# LPC1768_3.net
KiCad netlist of a schematic drawn in Altium Designer
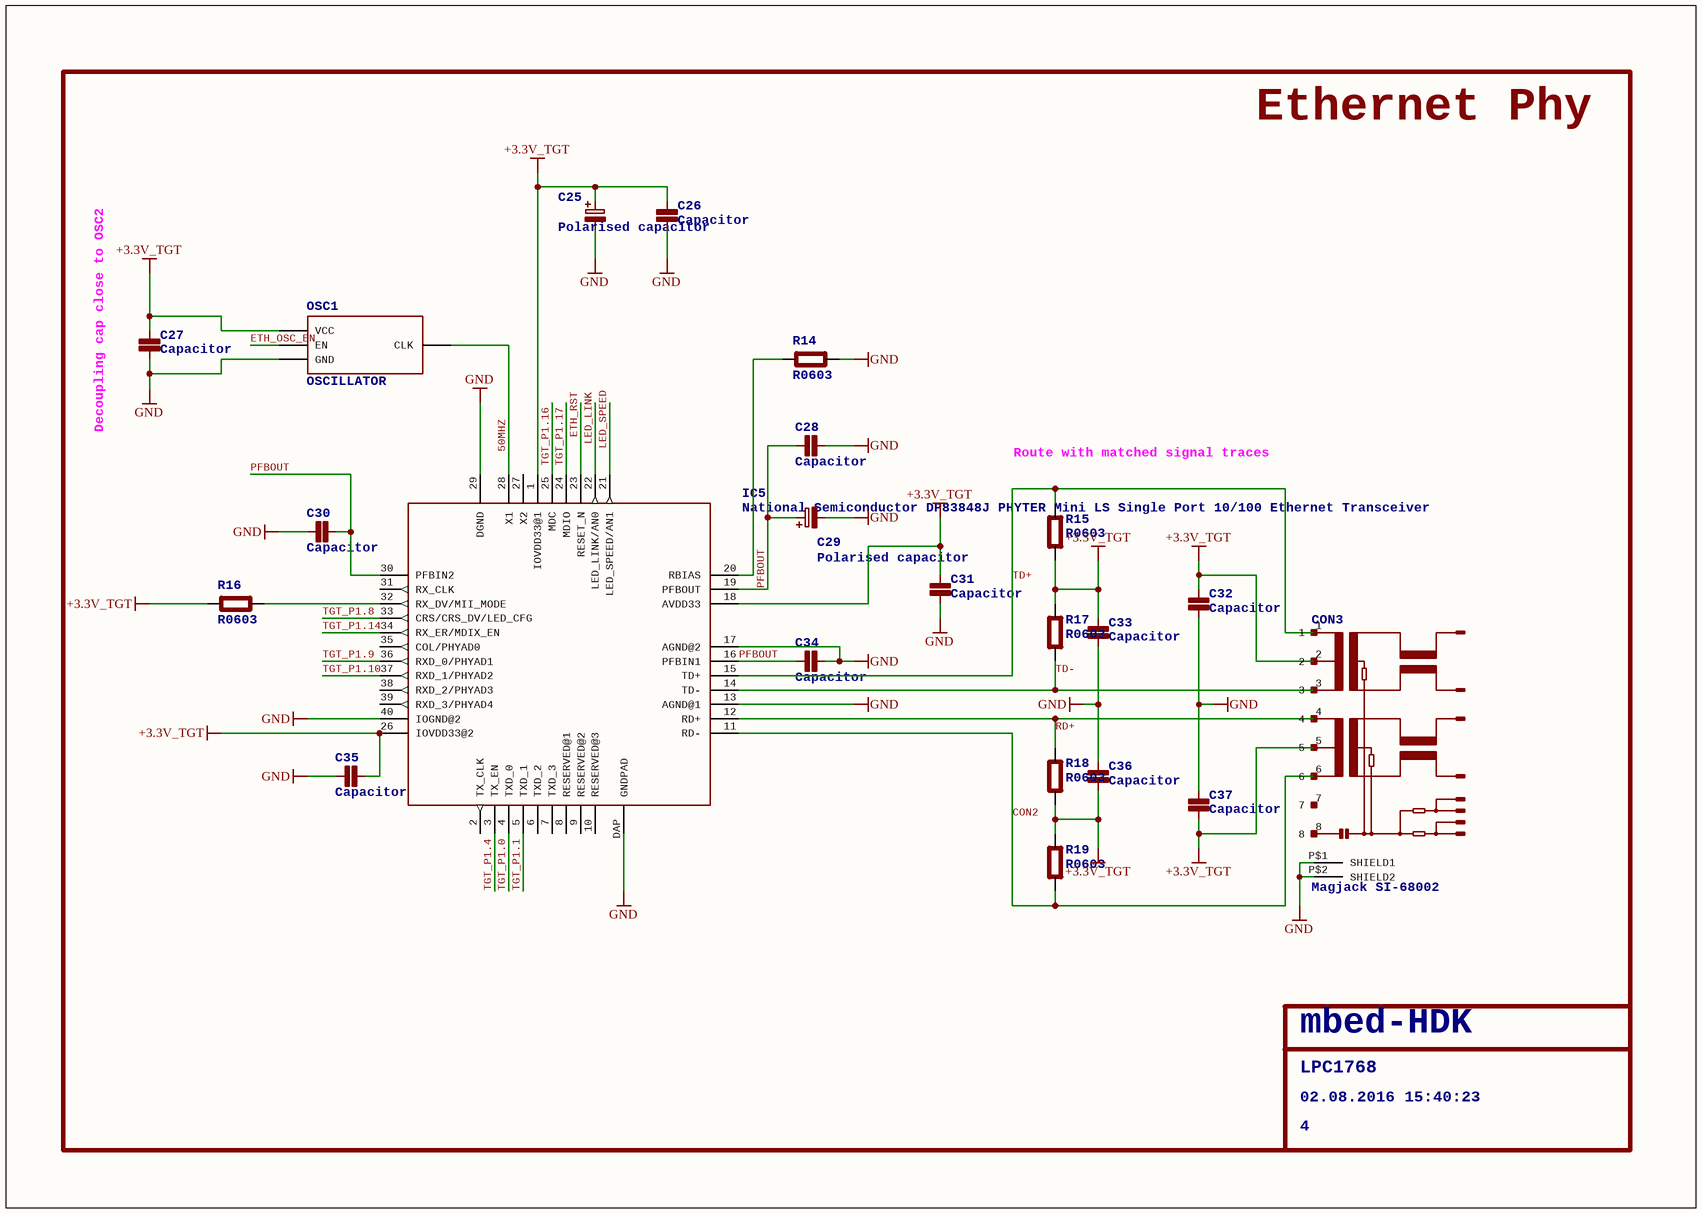
[diagram p0: LPC1768_3.SchDoc]

(export (version "E")
  (design (tool "Eeschema 10.0.6"))
  (components
    (comp (ref "C25")
      (value "Polarised capacitor")
      (footprint "CASE-B")
      (libsource (lib "mbed-HDK") (part "C-POLB"))
    )
    (comp (ref "C26") (value "Capacitor") (footprint "0603") (libsource (lib "mbed-HDK") (part "C0603")))
    (comp (ref "C27") (value "Capacitor") (footprint "0603") (libsource (lib "mbed-HDK") (part "C0603")))
    (comp (ref "C28") (value "Capacitor") (footprint "0603") (libsource (lib "") (part "C0603_2")))
    (comp (ref "C29")
      (value "Polarised capacitor")
      (footprint "CASE-B")
      (libsource (lib "") (part "C-POLB_1"))
    )
    (comp (ref "C30") (value "Capacitor") (footprint "0603") (libsource (lib "") (part "C0603_1")))
    (comp (ref "C31") (value "Capacitor") (footprint "0603") (libsource (lib "mbed-HDK") (part "C0603")))
    (comp (ref "C32") (value "Capacitor") (footprint "0603") (libsource (lib "mbed-HDK") (part "C0603")))
    (comp (ref "C33") (value "Capacitor") (footprint "0603") (libsource (lib "mbed-HDK") (part "C0603")))
    (comp (ref "C34") (value "Capacitor") (footprint "0603") (libsource (lib "") (part "C0603_1")))
    (comp (ref "C35") (value "Capacitor") (footprint "0603") (libsource (lib "") (part "C0603_2")))
    (comp (ref "C36") (value "Capacitor") (footprint "0603") (libsource (lib "mbed-HDK") (part "C0603")))
    (comp (ref "C37") (value "Capacitor") (footprint "0603") (libsource (lib "mbed-HDK") (part "C0603")))
    (comp (ref "CON3")
      (value "Magjack SI-68002")
      (footprint "RJ45")
      (libsource (lib "mbed-HDK") (part "RJ45"))
    )
    (comp (ref "IC5")
      (value "National Semiconductor DP83848J PHYTER Mini LS Single Port 10/100 Ethernet Transceiver")
      (footprint "LLP-40")
      (libsource (lib "mbed-HDK") (part "DP83848J"))
    )
    (comp (ref "OSC1")
      (value "OSCILLATOR")
      (footprint "3.2X.2.5")
      (libsource (lib "mbed-HDK") (part "OSCILLATOR"))
    )
    (comp (ref "R14") (value "R0603") (footprint "0603") (libsource (lib "mbed-HDK") (part "R0603")))
    (comp (ref "R15") (value "R0603") (footprint "0603") (libsource (lib "mbed-HDK") (part "R0603")))
    (comp (ref "R16") (value "R0603") (footprint "0603") (libsource (lib "mbed-HDK") (part "R0603")))
    (comp (ref "R17") (value "R0603") (footprint "0603") (libsource (lib "mbed-HDK") (part "R0603")))
    (comp (ref "R18") (value "R0603") (footprint "0603") (libsource (lib "mbed-HDK") (part "R0603")))
    (comp (ref "R19") (value "R0603") (footprint "0603") (libsource (lib "mbed-HDK") (part "R0603")))
  )
  (nets
    (net (code "1") (name "+3.3V_TGT") (class "Default")
      (node (ref "C25") (pin "1") (pinfunction "1_1") (pintype "passive"))
      (node (ref "C26") (pin "1") (pinfunction "P$1_1") (pintype "passive"))
      (node (ref "C27") (pin "1") (pinfunction "P$1_1") (pintype "passive"))
      (node (ref "C31") (pin "1") (pinfunction "P$1_1") (pintype "passive"))
      (node (ref "C32") (pin "1") (pinfunction "P$1_1") (pintype "passive"))
      (node (ref "C33") (pin "1") (pinfunction "P$1_1") (pintype "passive"))
      (node (ref "C35") (pin "1") (pinfunction "P$1_1") (pintype "passive"))
      (node (ref "C36") (pin "2") (pinfunction "P$2_2") (pintype "passive"))
      (node (ref "C37") (pin "2") (pinfunction "P$2_2") (pintype "passive"))
      (node (ref "CON3") (pin "2") (pinfunction "2_2") (pintype "passive"))
      (node (ref "CON3") (pin "5") (pinfunction "5_5") (pintype "passive"))
      (node (ref "IC5") (pin "1") (pinfunction "IOVDD33@1_1") (pintype "power_in"))
      (node (ref "IC5") (pin "18") (pinfunction "AVDD33_18") (pintype "power_in"))
      (node (ref "IC5") (pin "26") (pinfunction "IOVDD33@2_26") (pintype "power_in"))
      (node (ref "OSC1") (pin "P$4") (pinfunction "VCC_P$4") (pintype "passive"))
      (node (ref "R15") (pin "1") (pinfunction "P$1_1") (pintype "passive"))
      (node (ref "R16") (pin "1") (pinfunction "P$1_1") (pintype "passive"))
      (node (ref "R17") (pin "2") (pinfunction "P$2_2") (pintype "passive"))
      (node (ref "R18") (pin "1") (pinfunction "P$1_1") (pintype "passive"))
      (node (ref "R19") (pin "2") (pinfunction "P$2_2") (pintype "passive"))
    )
    (net (code "2") (name "/50MHZ") (class "Default")
      (node (ref "IC5") (pin "28") (pinfunction "X1_28") (pintype "passive"))
      (node (ref "OSC1") (pin "P$3") (pinfunction "CLK_P$3") (pintype "passive"))
    )
    (net (code "3") (name "/CON2") (class "Default")
      (node (ref "CON3") (pin "6") (pinfunction "6_6") (pintype "passive"))
      (node (ref "IC5") (pin "11") (pinfunction "RD-_11") (pintype "passive"))
      (node (ref "R19") (pin "1") (pinfunction "P$1_1") (pintype "passive"))
    )
    (net (code "4") (name "/ETH_OSC_EN") (class "Default")
      (node (ref "OSC1") (pin "P$1") (pinfunction "EN_P$1") (pintype "passive"))
    )
    (net (code "5") (name "/ETH_RST") (class "Default")
      (node (ref "IC5") (pin "23") (pinfunction "RESET_N_23") (pintype "passive"))
    )
    (net (code "6") (name "/LED_LINK") (class "Default")
      (node (ref "IC5") (pin "22") (pinfunction "LED_LINK/AN0_22") (pintype "output"))
    )
    (net (code "7") (name "/LED_SPEED") (class "Default")
      (node (ref "IC5") (pin "21") (pinfunction "LED_SPEED/AN1_21") (pintype "output"))
    )
    (net (code "8") (name "/PFBOUT") (class "Default")
      (node (ref "C28") (pin "2") (pinfunction "P$2_2") (pintype "passive"))
      (node (ref "C29") (pin "1") (pinfunction "1_1") (pintype "passive"))
      (node (ref "C30") (pin "2") (pinfunction "P$2_2") (pintype "passive"))
      (node (ref "C34") (pin "1") (pinfunction "P$1_1") (pintype "passive"))
      (node (ref "IC5") (pin "16") (pinfunction "PFBIN1_16") (pintype "passive"))
      (node (ref "IC5") (pin "19") (pinfunction "PFBOUT_19") (pintype "passive"))
      (node (ref "IC5") (pin "30") (pinfunction "PFBIN2_30") (pintype "passive"))
    )
    (net (code "9") (name "/RD+") (class "Default")
      (node (ref "CON3") (pin "4") (pinfunction "4_4") (pintype "passive"))
      (node (ref "IC5") (pin "12") (pinfunction "RD+_12") (pintype "passive"))
      (node (ref "R18") (pin "2") (pinfunction "P$2_2") (pintype "passive"))
    )
    (net (code "10") (name "/TD+") (class "Default")
      (node (ref "CON3") (pin "1") (pinfunction "1_1") (pintype "passive"))
      (node (ref "IC5") (pin "15") (pinfunction "TD+_15") (pintype "passive"))
      (node (ref "R15") (pin "2") (pinfunction "P$2_2") (pintype "passive"))
    )
    (net (code "11") (name "/TD-") (class "Default")
      (node (ref "CON3") (pin "3") (pinfunction "3_3") (pintype "passive"))
      (node (ref "IC5") (pin "14") (pinfunction "TD-_14") (pintype "passive"))
      (node (ref "R17") (pin "1") (pinfunction "P$1_1") (pintype "passive"))
    )
    (net (code "12") (name "/TGT_P1.0") (class "Default")
      (node (ref "IC5") (pin "4") (pinfunction "TXD_0_4") (pintype "passive"))
    )
    (net (code "13") (name "/TGT_P1.1") (class "Default")
      (node (ref "IC5") (pin "5") (pinfunction "TXD_1_5") (pintype "passive"))
    )
    (net (code "14") (name "/TGT_P1.4") (class "Default")
      (node (ref "IC5") (pin "3") (pinfunction "TX_EN_3") (pintype "passive"))
    )
    (net (code "15") (name "/TGT_P1.8") (class "Default")
      (node (ref "IC5") (pin "33") (pinfunction "CRS/CRS_DV/LED_CFG_33") (pintype "output"))
    )
    (net (code "16") (name "/TGT_P1.9") (class "Default")
      (node (ref "IC5") (pin "36") (pinfunction "RXD_0/PHYAD1_36") (pintype "output"))
    )
    (net (code "17") (name "/TGT_P1.10") (class "Default")
      (node (ref "IC5") (pin "37") (pinfunction "RXD_1/PHYAD2_37") (pintype "output"))
    )
    (net (code "18") (name "/TGT_P1.14") (class "Default")
      (node (ref "IC5") (pin "34") (pinfunction "RX_ER/MDIX_EN_34") (pintype "output"))
    )
    (net (code "19") (name "/TGT_P1.16") (class "Default")
      (node (ref "IC5") (pin "25") (pinfunction "MDC_25") (pintype "passive"))
    )
    (net (code "20") (name "/TGT_P1.17") (class "Default")
      (node (ref "IC5") (pin "24") (pinfunction "MDIO_24") (pintype "passive"))
    )
    (net (code "21") (name "GND") (class "Default")
      (node (ref "C25") (pin "2") (pinfunction "2_2") (pintype "passive"))
      (node (ref "C26") (pin "2") (pinfunction "P$2_2") (pintype "passive"))
      (node (ref "C27") (pin "2") (pinfunction "P$2_2") (pintype "passive"))
      (node (ref "C28") (pin "1") (pinfunction "P$1_1") (pintype "passive"))
      (node (ref "C29") (pin "2") (pinfunction "2_2") (pintype "passive"))
      (node (ref "C30") (pin "1") (pinfunction "P$1_1") (pintype "passive"))
      (node (ref "C31") (pin "2") (pinfunction "P$2_2") (pintype "passive"))
      (node (ref "C32") (pin "2") (pinfunction "P$2_2") (pintype "passive"))
      (node (ref "C33") (pin "2") (pinfunction "P$2_2") (pintype "passive"))
      (node (ref "C34") (pin "2") (pinfunction "P$2_2") (pintype "passive"))
      (node (ref "C35") (pin "2") (pinfunction "P$2_2") (pintype "passive"))
      (node (ref "C36") (pin "1") (pinfunction "P$1_1") (pintype "passive"))
      (node (ref "C37") (pin "1") (pinfunction "P$1_1") (pintype "passive"))
      (node (ref "CON3") (pin "P$1") (pinfunction "SHIELD1_P$1") (pintype "passive"))
      (node (ref "CON3") (pin "P$2") (pinfunction "SHIELD2_P$2") (pintype "passive"))
      (node (ref "IC5") (pin "13") (pinfunction "AGND@1_13") (pintype "power_in"))
      (node (ref "IC5") (pin "17") (pinfunction "AGND@2_17") (pintype "power_in"))
      (node (ref "IC5") (pin "29") (pinfunction "DGND_29") (pintype "power_in"))
      (node (ref "IC5") (pin "40") (pinfunction "IOGND@2_40") (pintype "power_in"))
      (node (ref "IC5") (pin "DAP") (pinfunction "GNDPAD_DAP") (pintype "power_in"))
      (node (ref "OSC1") (pin "P$2") (pinfunction "GND_P$2") (pintype "passive"))
      (node (ref "R14") (pin "1") (pinfunction "P$1_1") (pintype "passive"))
    )
    (net (code "22") (name "Net-(IC5-RBIAS)") (class "Default")
      (node (ref "IC5") (pin "20") (pinfunction "RBIAS_20") (pintype "passive"))
      (node (ref "R14") (pin "2") (pinfunction "P$2_2") (pintype "passive"))
    )
    (net (code "23") (name "Net-(IC5-RX_DV{slash}MII_MODE)") (class "Default")
      (node (ref "IC5") (pin "32") (pinfunction "RX_DV/MII_MODE_32") (pintype "output"))
      (node (ref "R16") (pin "2") (pinfunction "P$2_2") (pintype "passive"))
    )
    (net (code "24") (name "unconnected-(CON3-Pad7)") (class "Default")
      (node (ref "CON3") (pin "7") (pinfunction "7_7") (pintype "passive"))
    )
    (net (code "25") (name "unconnected-(CON3-Pad8)") (class "Default")
      (node (ref "CON3") (pin "8") (pinfunction "8_8") (pintype "passive"))
    )
    (net (code "26") (name "unconnected-(IC5-COL{slash}PHYAD0-Pad35)") (class "Default")
      (node (ref "IC5") (pin "35") (pinfunction "COL/PHYAD0_35") (pintype "output"))
    )
    (net (code "27") (name "unconnected-(IC5-RESERVED@1-Pad8)") (class "Default")
      (node (ref "IC5") (pin "8") (pinfunction "RESERVED@1_8") (pintype "passive"))
    )
    (net (code "28") (name "unconnected-(IC5-RESERVED@2-Pad9)") (class "Default")
      (node (ref "IC5") (pin "9") (pinfunction "RESERVED@2_9") (pintype "passive"))
    )
    (net (code "29") (name "unconnected-(IC5-RESERVED@3-Pad10)") (class "Default")
      (node (ref "IC5") (pin "10") (pinfunction "RESERVED@3_10") (pintype "passive"))
    )
    (net (code "30") (name "unconnected-(IC5-RXD_2{slash}PHYAD3-Pad38)") (class "Default")
      (node (ref "IC5") (pin "38") (pinfunction "RXD_2/PHYAD3_38") (pintype "output"))
    )
    (net (code "31") (name "unconnected-(IC5-RXD_3{slash}PHYAD4-Pad39)") (class "Default")
      (node (ref "IC5") (pin "39") (pinfunction "RXD_3/PHYAD4_39") (pintype "output"))
    )
    (net (code "32") (name "unconnected-(IC5-RX_CLK-Pad31)") (class "Default")
      (node (ref "IC5") (pin "31") (pinfunction "RX_CLK_31") (pintype "output"))
    )
    (net (code "33") (name "unconnected-(IC5-TXD_2-Pad6)") (class "Default")
      (node (ref "IC5") (pin "6") (pinfunction "TXD_2_6") (pintype "passive"))
    )
    (net (code "34") (name "unconnected-(IC5-TXD_3-Pad7)") (class "Default")
      (node (ref "IC5") (pin "7") (pinfunction "TXD_3_7") (pintype "passive"))
    )
    (net (code "35") (name "unconnected-(IC5-TX_CLK-Pad2)") (class "Default")
      (node (ref "IC5") (pin "2") (pinfunction "TX_CLK_2") (pintype "output"))
    )
    (net (code "36") (name "unconnected-(IC5-X2-Pad27)") (class "Default")
      (node (ref "IC5") (pin "27") (pinfunction "X2_27") (pintype "passive"))
    )
  )
)
